# RowDriver.net
KiCad netlist of a schematic drawn in EAGLE
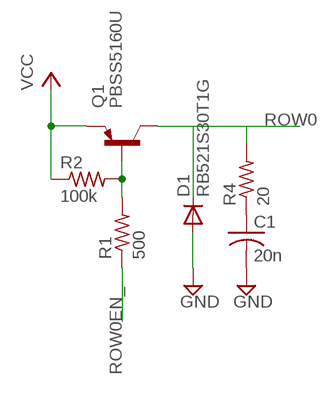
[diagram p0: schematic, sheet 1]

(export (version "E")
  (design (tool "Eeschema 10.0.6"))
  (components
    (comp (ref "C1")
      (value "20n")
      (footprint "eagle-import:C0805")
      (libsource (lib "eagle-import") (part "C-USC0805"))
    )
    (comp (ref "D1")
      (value "RB521S30T1G")
      (footprint "eagle-import:SOD523")
      (libsource (lib "eagle-import") (part "DIODE-SOD523"))
    )
    (comp (ref "Q1")
      (value "PBSS5160U")
      (footprint "eagle-import:SOT23-BCE")
      (libsource (lib "eagle-import") (part "-PNP-SOT23-BCE"))
    )
    (comp (ref "R1")
      (value "500")
      (footprint "eagle-import:R0805")
      (libsource (lib "eagle-import") (part "R-US_R0805"))
    )
    (comp (ref "R2")
      (value "100k")
      (footprint "eagle-import:R0805")
      (libsource (lib "eagle-import") (part "R-US_R0805"))
    )
    (comp (ref "R4")
      (value "20")
      (footprint "eagle-import:R0805")
      (libsource (lib "eagle-import") (part "R-US_R0805"))
    )
  )
  (nets
    (net (code "1") (name "/ROW0") (class "Default")
      (node (ref "D1") (pin "C") (pinfunction "C_C") (pintype "passive"))
      (node (ref "Q1") (pin "C") (pinfunction "C_C") (pintype "passive"))
      (node (ref "R4") (pin "2") (pinfunction "2_2") (pintype "passive"))
    )
    (net (code "2") (name "/ROW0EN_") (class "Default")
      (node (ref "R1") (pin "1") (pinfunction "1_1") (pintype "passive"))
    )
    (net (code "3") (name "GND") (class "Default")
      (node (ref "C1") (pin "2") (pinfunction "2_2") (pintype "passive"))
      (node (ref "D1") (pin "A") (pinfunction "A_A") (pintype "passive"))
    )
    (net (code "4") (name "Net-(C1-Pad1)") (class "Default")
      (node (ref "C1") (pin "1") (pinfunction "1_1") (pintype "passive"))
      (node (ref "R4") (pin "1") (pinfunction "1_1") (pintype "passive"))
    )
    (net (code "5") (name "Net-(Q1-PadB)") (class "Default")
      (node (ref "Q1") (pin "B") (pinfunction "B_B") (pintype "passive"))
      (node (ref "R1") (pin "2") (pinfunction "2_2") (pintype "passive"))
      (node (ref "R2") (pin "2") (pinfunction "2_2") (pintype "passive"))
    )
    (net (code "6") (name "VCC") (class "Default")
      (node (ref "Q1") (pin "E") (pinfunction "E_E") (pintype "passive"))
      (node (ref "R2") (pin "1") (pinfunction "1_1") (pintype "passive"))
    )
  )
)
